# main.net
KiCad netlist of a schematic drawn in EAGLE
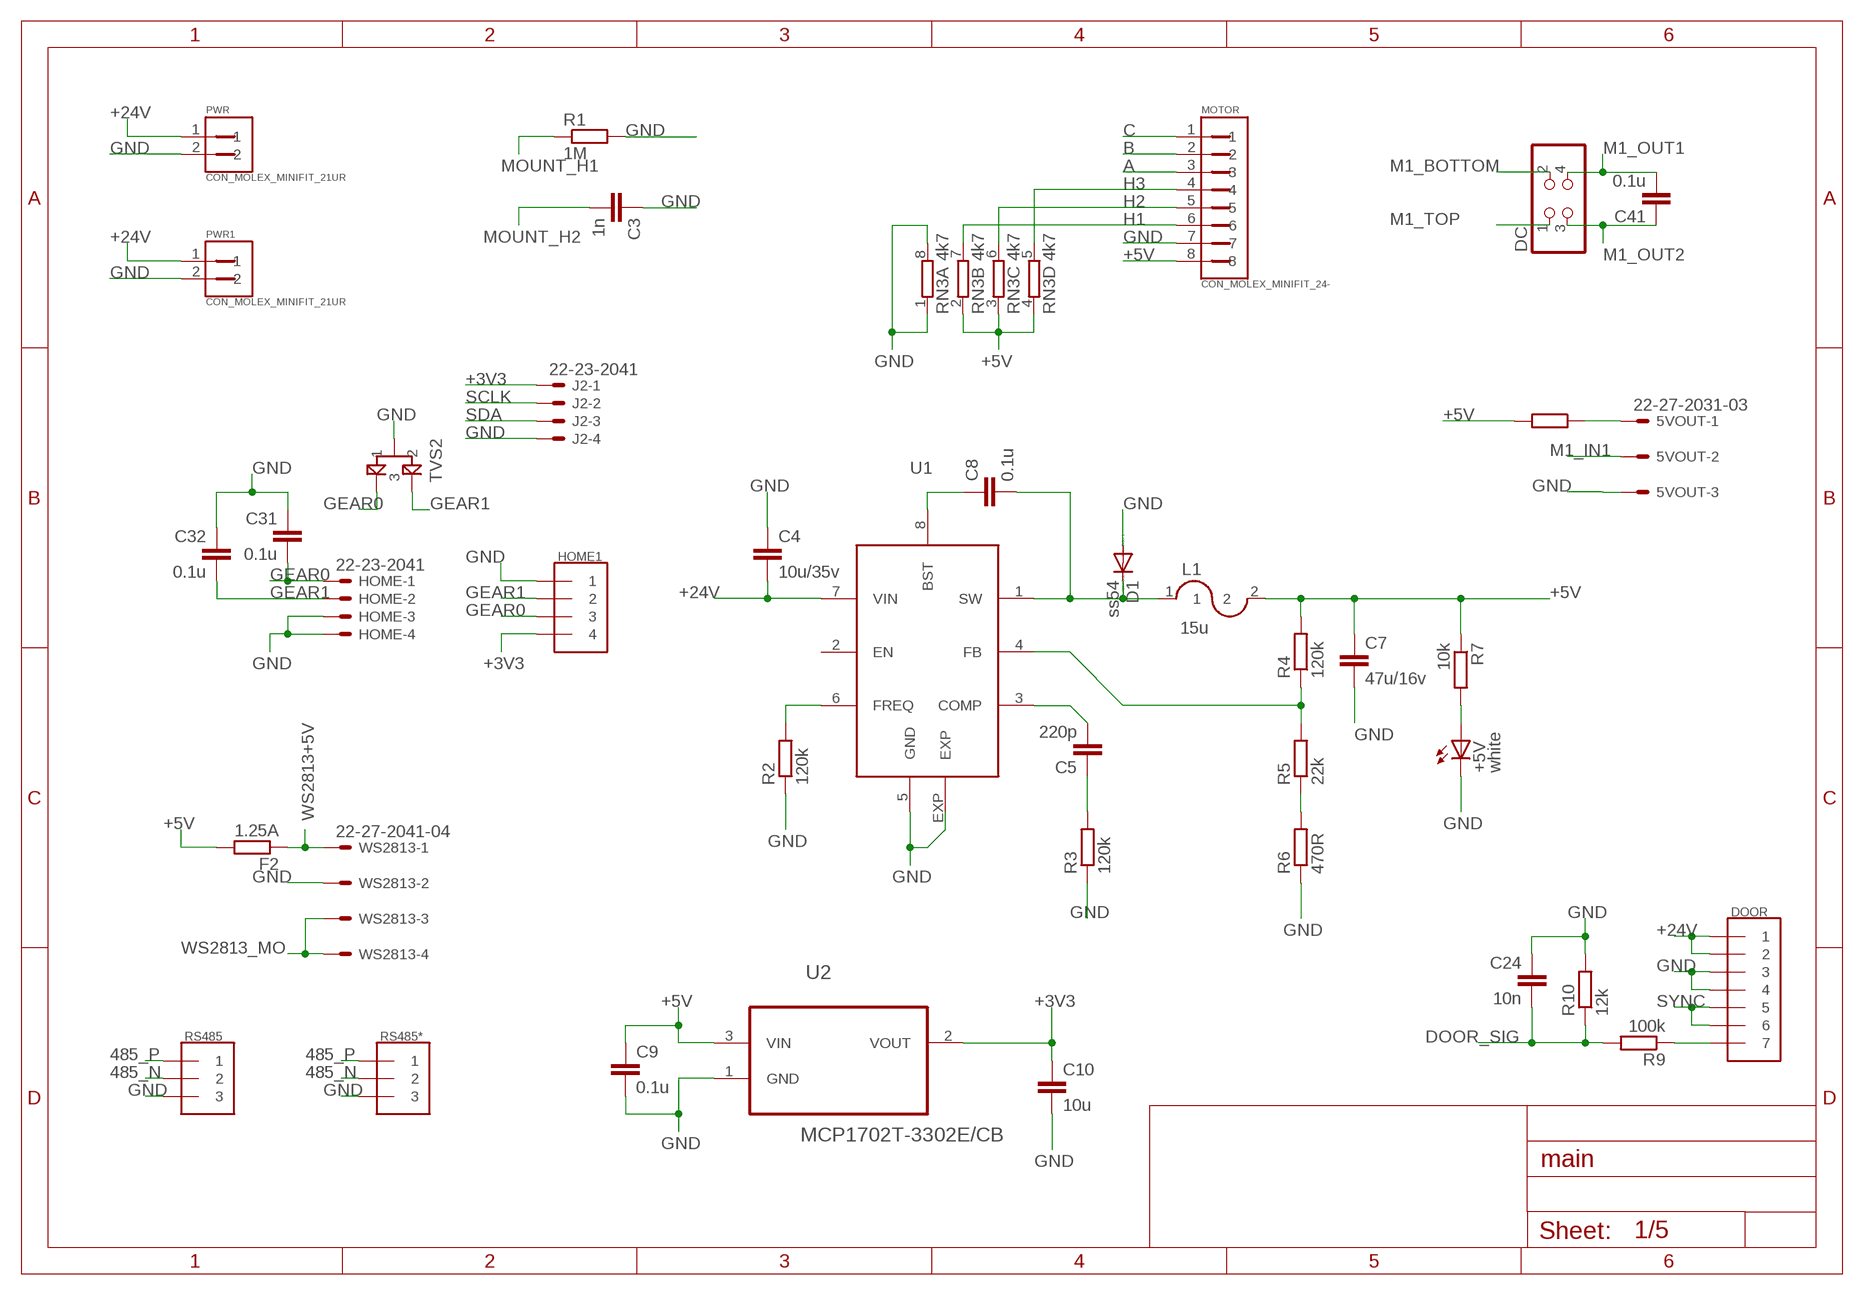
[diagram p0: schematic, sheet 1]
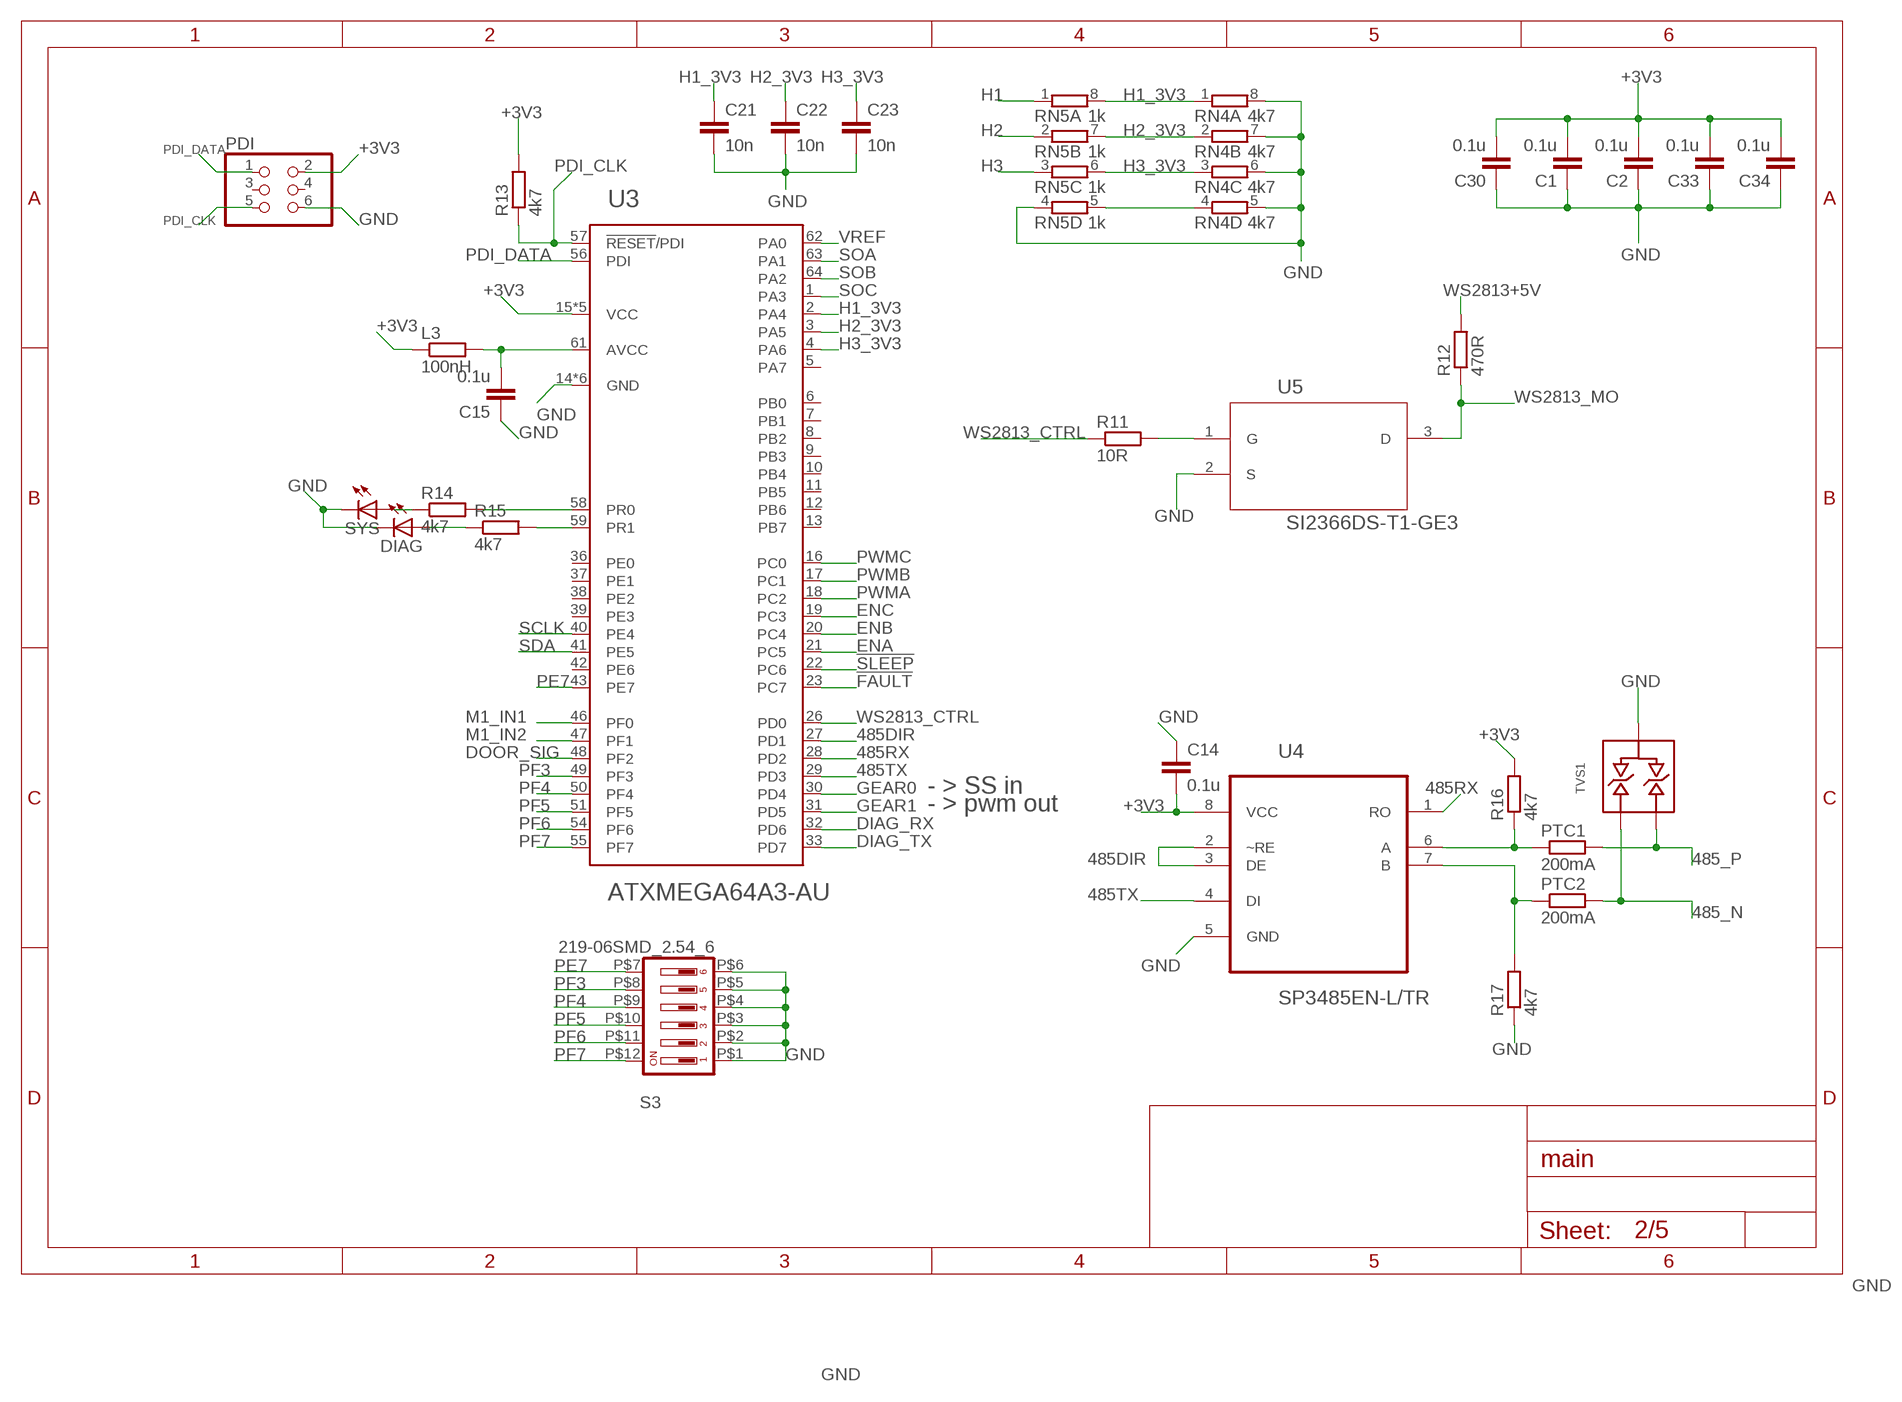
[diagram p1: schematic, sheet 2]
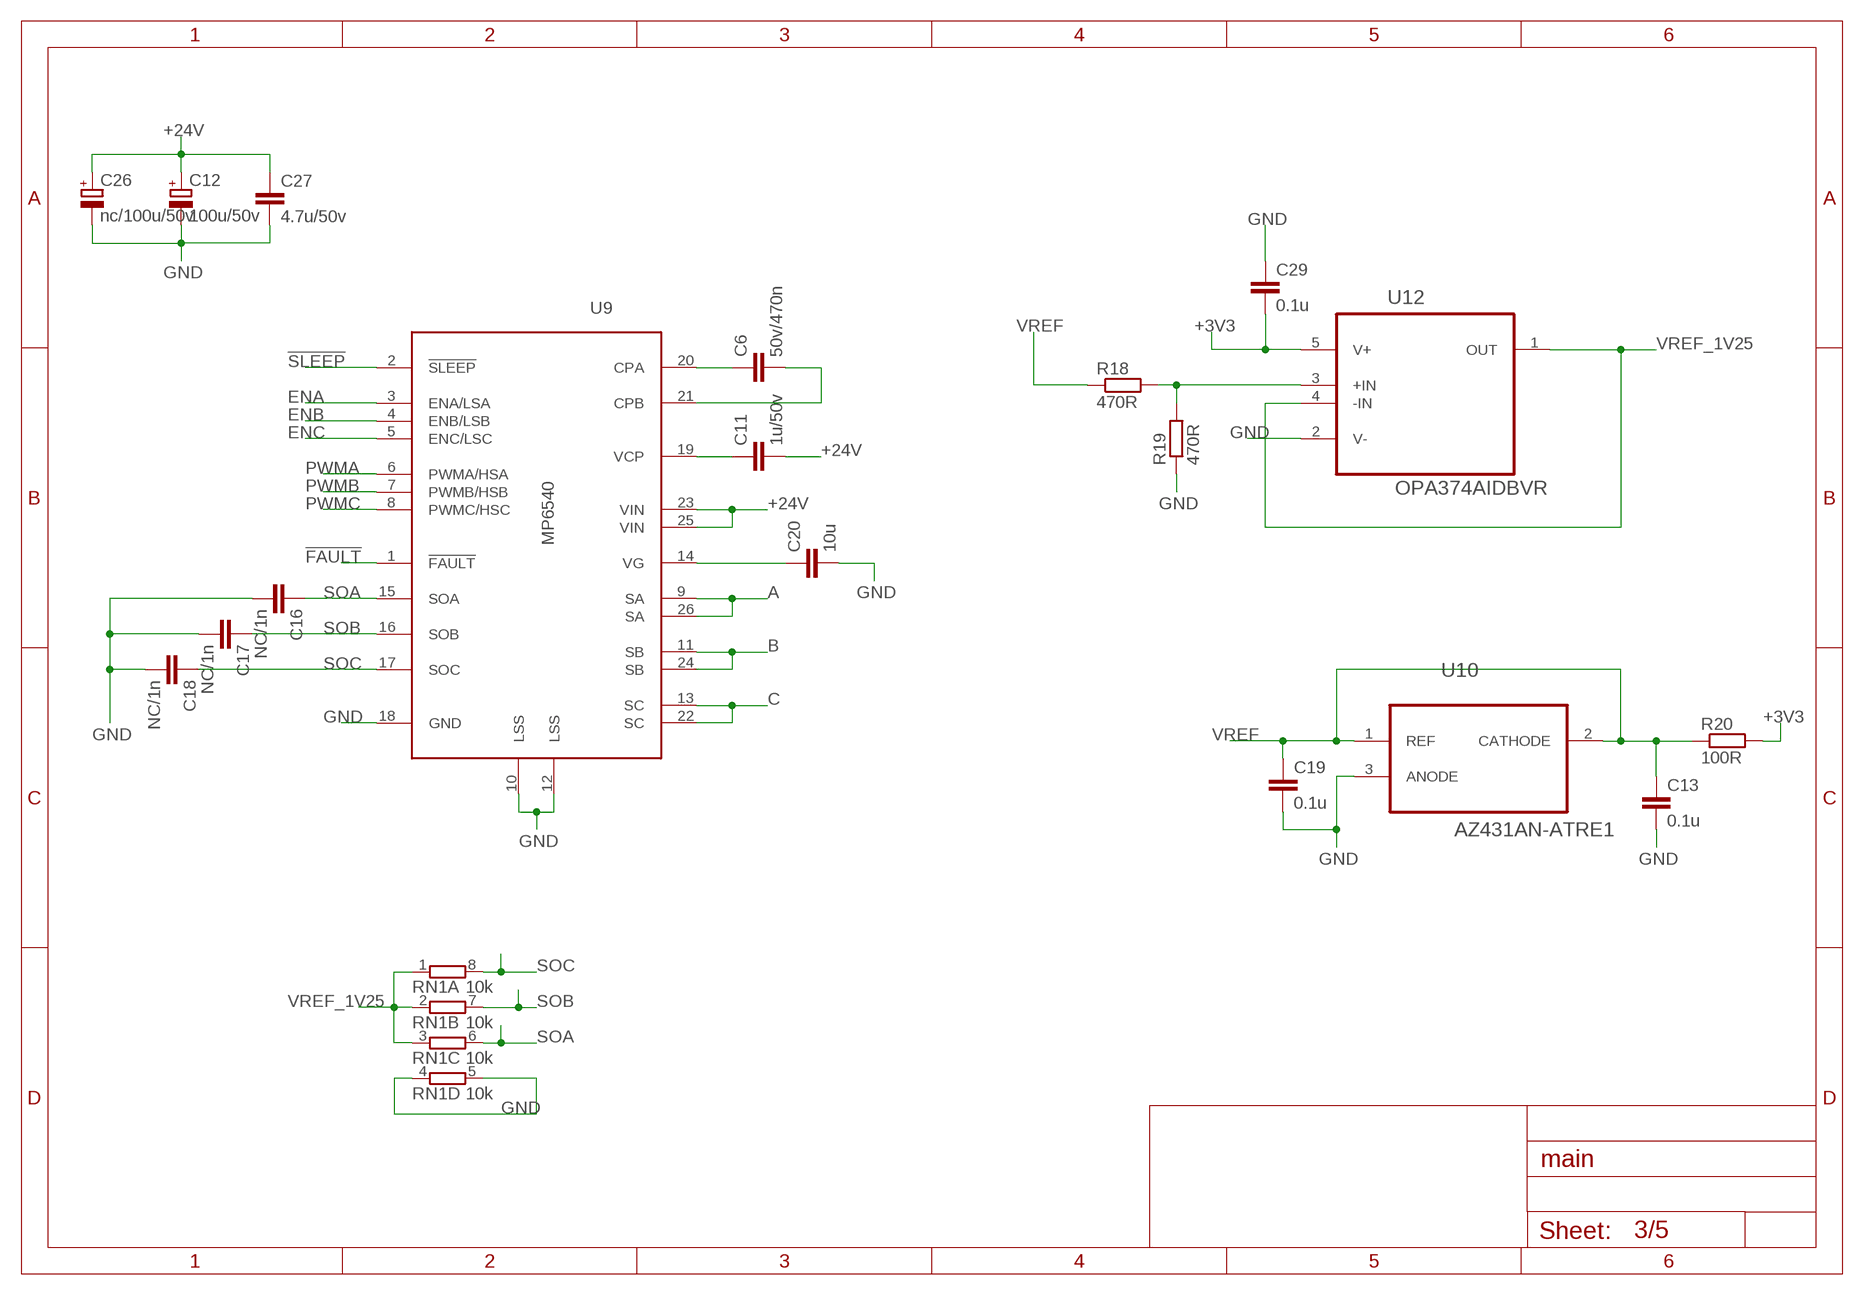
[diagram p2: schematic, sheet 3]
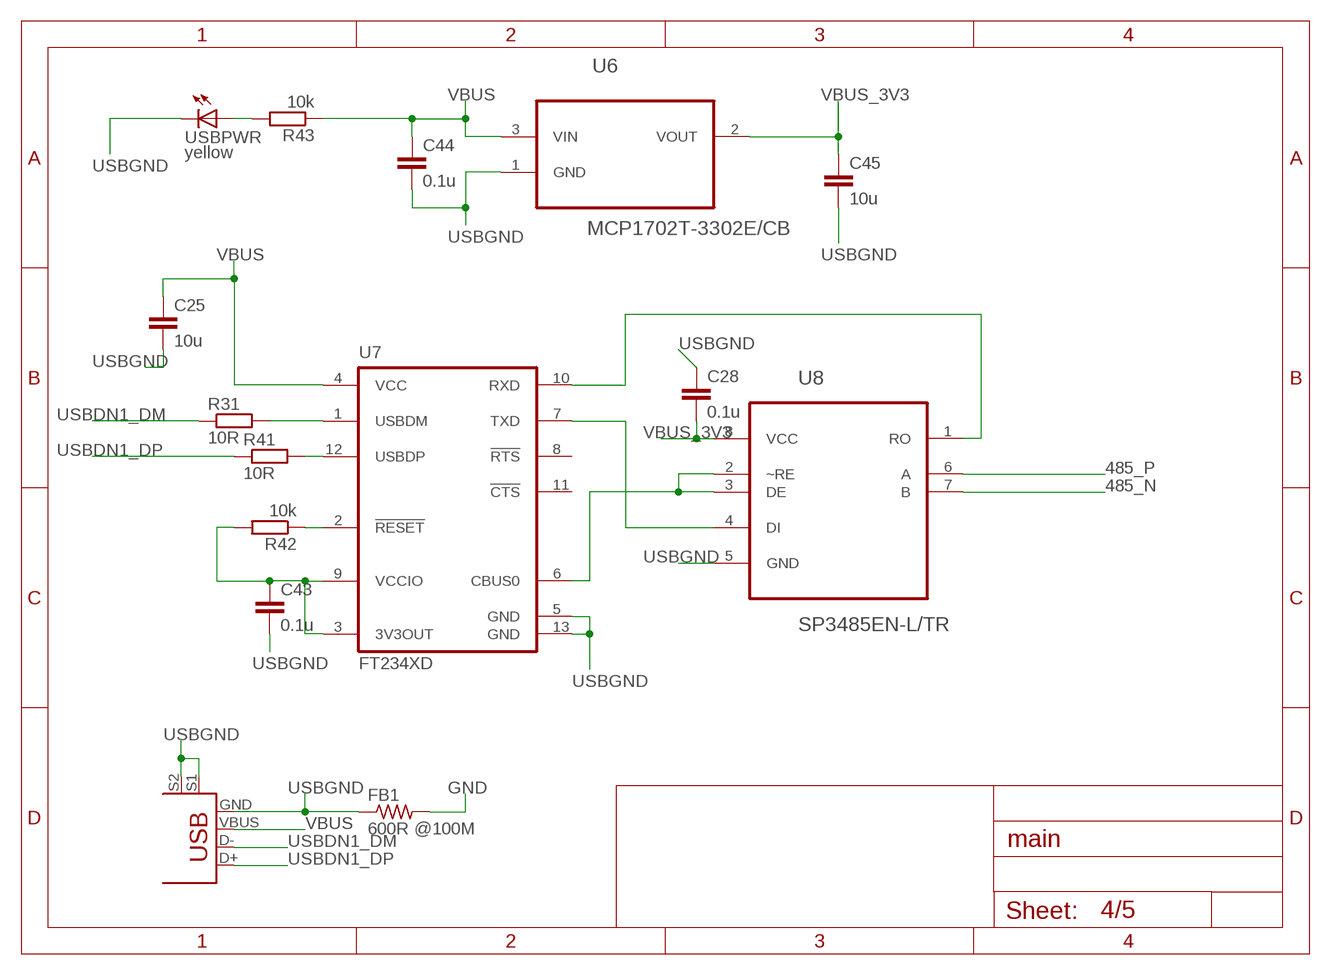
[diagram p3: schematic, sheet 4]
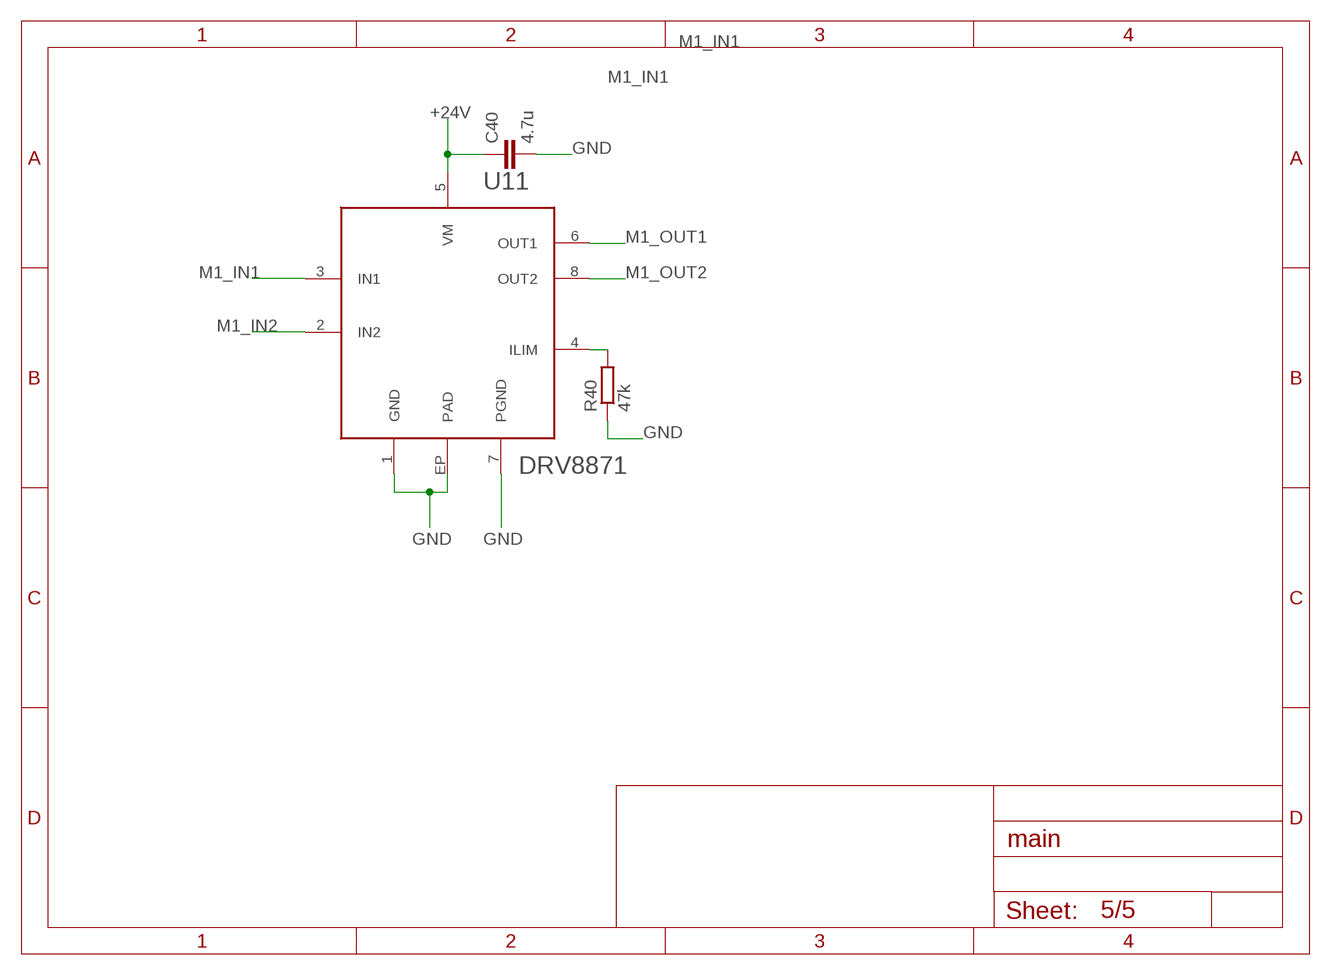
[diagram p4: schematic, sheet 5]

(export (version "E")
  (design (tool "Eeschema 10.0.6"))
  (components
    (comp (ref "C1")
      (value "0.1u")
      (footprint "eagle-import:C0603")
      (libsource (lib "eagle-import") (part "C-EUC0603"))
    )
    (comp (ref "C2")
      (value "0.1u")
      (footprint "eagle-import:C0603")
      (libsource (lib "eagle-import") (part "C-EUC0603"))
    )
    (comp (ref "C14")
      (value "0.1u")
      (footprint "eagle-import:C0603")
      (libsource (lib "eagle-import") (part "C-EUC0603"))
    )
    (comp (ref "C15")
      (value "0.1u")
      (footprint "eagle-import:C0603")
      (libsource (lib "eagle-import") (part "C-EUC0603"))
    )
    (comp (ref "C21")
      (value "10n")
      (footprint "eagle-import:C0603")
      (libsource (lib "eagle-import") (part "C-EUC0603"))
    )
    (comp (ref "C22")
      (value "10n")
      (footprint "eagle-import:C0603")
      (libsource (lib "eagle-import") (part "C-EUC0603"))
    )
    (comp (ref "C23")
      (value "10n")
      (footprint "eagle-import:C0603")
      (libsource (lib "eagle-import") (part "C-EUC0603"))
    )
    (comp (ref "C30")
      (value "0.1u")
      (footprint "eagle-import:C0603")
      (libsource (lib "eagle-import") (part "C-EUC0603"))
    )
    (comp (ref "C33")
      (value "0.1u")
      (footprint "eagle-import:C0603")
      (libsource (lib "eagle-import") (part "C-EUC0603"))
    )
    (comp (ref "C34")
      (value "0.1u")
      (footprint "eagle-import:C0603")
      (libsource (lib "eagle-import") (part "C-EUC0603"))
    )
    (comp (ref "DIAG")
      (value "LEDSML0603")
      (footprint "eagle-import:SML0603")
      (libsource (lib "eagle-import") (part "LEDSML0603"))
    )
    (comp (ref "L3")
      (value "100nH")
      (footprint "eagle-import:R0603")
      (libsource (lib "eagle-import") (part "R-EU_R0603"))
    )
    (comp (ref "PDI")
      (value "PINHD-2X3")
      (footprint "eagle-import:2X03")
      (libsource (lib "eagle-import") (part "PINHD-2X3"))
    )
    (comp (ref "PTC1")
      (value "200mA")
      (footprint "eagle-import:R0805")
      (libsource (lib "eagle-import") (part "R-EU_R0805"))
    )
    (comp (ref "PTC2")
      (value "200mA")
      (footprint "eagle-import:R0805")
      (libsource (lib "eagle-import") (part "R-EU_R0805"))
    )
    (comp (ref "R11")
      (value "10R")
      (footprint "eagle-import:R0603")
      (libsource (lib "eagle-import") (part "R-EU_R0603"))
    )
    (comp (ref "R12")
      (value "470R")
      (footprint "eagle-import:R0603")
      (libsource (lib "eagle-import") (part "R-EU_R0603"))
    )
    (comp (ref "R13")
      (value "4k7")
      (footprint "eagle-import:R0603")
      (libsource (lib "eagle-import") (part "R-EU_R0603"))
    )
    (comp (ref "R14")
      (value "4k7")
      (footprint "eagle-import:R0603")
      (libsource (lib "eagle-import") (part "R-EU_R0603"))
    )
    (comp (ref "R15")
      (value "4k7")
      (footprint "eagle-import:R0603")
      (libsource (lib "eagle-import") (part "R-EU_R0603"))
    )
    (comp (ref "R16")
      (value "4k7")
      (footprint "eagle-import:R0603")
      (libsource (lib "eagle-import") (part "R-EU_R0603"))
    )
    (comp (ref "R17")
      (value "4k7")
      (footprint "eagle-import:R0603")
      (libsource (lib "eagle-import") (part "R-EU_R0603"))
    )
    (comp (ref "RN4")
      (value "4k7")
      (footprint "eagle-import:EXB38V")
      (libsource (lib "eagle-import") (part "4R-NEXB38V"))
    )
    (comp (ref "RN5")
      (value "1k")
      (footprint "eagle-import:EXB38V")
      (libsource (lib "eagle-import") (part "4R-NEXB38V"))
    )
    (comp (ref "S3")
      (value "219-06SMD_2.54_6")
      (footprint "eagle-import:SMD-2.54-6")
      (libsource (lib "eagle-import") (part "219-06SMD_2.54_6"))
    )
    (comp (ref "SYS")
      (value "LEDSML0603")
      (footprint "eagle-import:SML0603")
      (libsource (lib "eagle-import") (part "LEDSML0603"))
    )
    (comp (ref "TVS1")
      (value "SM712")
      (footprint "eagle-import:SOT23")
      (libsource (lib "eagle-import") (part "SM712"))
    )
    (comp (ref "U3")
      (value "ATXMEGA64A3-AU")
      (footprint "eagle-import:TQFP-64A-64")
      (libsource (lib "eagle-import") (part "ATXMEGA64A3-AU"))
    )
    (comp (ref "U4")
      (value "SP3485EN-L/TR")
      (footprint "eagle-import:SOIC127P600X175-8N")
      (fields (field (name "MPN") "MAX3485CSA+"))
      (libsource (lib "eagle-import") (part "MAX3485CSA+"))
    )
    (comp (ref "U5")
      (value "SI2366DS-T1-GE3")
      (footprint "eagle-import:SOT95P237X112-3N")
      (libsource (lib "eagle-import") (part "SI2366DS-T1-GE3"))
    )
    (comp (ref "C25")
      (value "10u")
      (footprint "eagle-import:C0603")
      (libsource (lib "eagle-import") (part "C-EUC0603"))
    )
    (comp (ref "C28")
      (value "0.1u")
      (footprint "eagle-import:C0603")
      (libsource (lib "eagle-import") (part "C-EUC0603"))
    )
    (comp (ref "C43")
      (value "0.1u")
      (footprint "eagle-import:C0603")
      (libsource (lib "eagle-import") (part "C-EUC0603"))
    )
    (comp (ref "C44")
      (value "0.1u")
      (footprint "eagle-import:C0603")
      (libsource (lib "eagle-import") (part "C-EUC0603"))
    )
    (comp (ref "C45")
      (value "10u")
      (footprint "eagle-import:C0603")
      (libsource (lib "eagle-import") (part "C-EUC0603"))
    )
    (comp (ref "FB1")
      (value "600R @100M")
      (footprint "eagle-import:R0805")
      (libsource (lib "eagle-import") (part "R-US_R0805"))
    )
    (comp (ref "R31")
      (value "10R")
      (footprint "eagle-import:R0603")
      (libsource (lib "eagle-import") (part "R-EU_R0603"))
    )
    (comp (ref "R41")
      (value "10R")
      (footprint "eagle-import:R0603")
      (libsource (lib "eagle-import") (part "R-EU_R0603"))
    )
    (comp (ref "R42")
      (value "10k")
      (footprint "eagle-import:R0603")
      (libsource (lib "eagle-import") (part "R-EU_R0603"))
    )
    (comp (ref "R43")
      (value "10k")
      (footprint "eagle-import:R0603")
      (libsource (lib "eagle-import") (part "R-EU_R0603"))
    )
    (comp (ref "U6")
      (value "MCP1702T-3302E/CB")
      (footprint "eagle-import:SOT95P255X145-3N")
      (libsource (lib "eagle-import") (part "MCP1702T-3302E/CB"))
    )
    (comp (ref "U7")
      (value "FT234XD")
      (footprint "eagle-import:DFN12")
      (libsource (lib "eagle-import") (part "FT234XD"))
    )
    (comp (ref "U8")
      (value "SP3485EN-L/TR")
      (footprint "eagle-import:SOIC127P600X175-8N")
      (fields (field (name "MPN") "MAX3485CSA+"))
      (libsource (lib "eagle-import") (part "MAX3485CSA+"))
    )
    (comp (ref "USBPWR")
      (value "yellow")
      (footprint "eagle-import:SML0603")
      (libsource (lib "eagle-import") (part "LEDSML0603"))
    )
    (comp (ref "USBUP")
      (value "USB+SHIELD")
      (footprint "eagle-import:USB-B-PTH")
      (libsource (lib "eagle-import") (part "USB+SHIELD"))
    )
    (comp (ref "C40")
      (value "4.7u")
      (footprint "eagle-import:C0805")
      (libsource (lib "eagle-import") (part "C-EUC0805"))
    )
    (comp (ref "R40")
      (value "47k")
      (footprint "eagle-import:R0603")
      (libsource (lib "eagle-import") (part "R-EU_R0603"))
    )
    (comp (ref "U11")
      (value "DRV8871")
      (footprint "eagle-import:8HSOIC")
      (libsource (lib "eagle-import") (part "DRV8871"))
    )
    (comp (ref "+5V")
      (value "white")
      (footprint "eagle-import:SML0603")
      (libsource (lib "eagle-import") (part "LEDSML0603"))
    )
    (comp (ref "5VOUT")
      (value "22-27-2031-03")
      (footprint "eagle-import:6410-03")
      (libsource (lib "eagle-import") (part "22-?-0327-2031"))
    )
    (comp (ref "C3")
      (value "1n")
      (footprint "eagle-import:C0603")
      (libsource (lib "eagle-import") (part "C-EUC0603"))
    )
    (comp (ref "C4")
      (value "10u/35v")
      (footprint "eagle-import:C1206")
      (libsource (lib "eagle-import") (part "C-EUC1206"))
    )
    (comp (ref "C5")
      (value "220p")
      (footprint "eagle-import:C0603")
      (libsource (lib "eagle-import") (part "C-EUC0603"))
    )
    (comp (ref "C7")
      (value "47u/16v")
      (footprint "eagle-import:C1206")
      (libsource (lib "eagle-import") (part "C-EUC1206"))
    )
    (comp (ref "C8")
      (value "0.1u")
      (footprint "eagle-import:C0603")
      (libsource (lib "eagle-import") (part "C-EUC0603"))
    )
    (comp (ref "C9")
      (value "0.1u")
      (footprint "eagle-import:C0603")
      (libsource (lib "eagle-import") (part "C-EUC0603"))
    )
    (comp (ref "C10")
      (value "10u")
      (footprint "eagle-import:C0603")
      (libsource (lib "eagle-import") (part "C-EUC0603"))
    )
    (comp (ref "C24")
      (value "10n")
      (footprint "eagle-import:C0603")
      (libsource (lib "eagle-import") (part "C-EUC0603"))
    )
    (comp (ref "C31")
      (value "0.1u")
      (footprint "eagle-import:C0603")
      (libsource (lib "eagle-import") (part "C-EUC0603"))
    )
    (comp (ref "C32")
      (value "0.1u")
      (footprint "eagle-import:C0603")
      (libsource (lib "eagle-import") (part "C-EUC0603"))
    )
    (comp (ref "C41")
      (value "0.1u")
      (footprint "eagle-import:C0603")
      (libsource (lib "eagle-import") (part "C-EUC0603"))
    )
    (comp (ref "D1")
      (value "ss54")
      (footprint "eagle-import:DO214BA")
      (libsource (lib "eagle-import") (part "DIODE-DO214BA"))
    )
    (comp (ref "DC")
      (value "430450414")
      (footprint "eagle-import:4304504-TH")
      (libsource (lib "eagle-import") (part "430450414"))
    )
    (comp (ref "DOOR")
      (value "1LINE_SOCKET_2MM_7")
      (footprint "eagle-import:1LINE_SOCKET_2MM_7")
      (libsource (lib "eagle-import") (part "1LINE_SOCKET_2MM_7"))
    )
    (comp (ref "F1")
      (value "1.25A")
      (footprint "eagle-import:R1206")
      (libsource (lib "eagle-import") (part "R-EU_R1206"))
    )
    (comp (ref "F2")
      (value "1.25A")
      (footprint "eagle-import:R1206")
      (libsource (lib "eagle-import") (part "R-EU_R1206"))
    )
    (comp (ref "HOME")
      (value "22-23-2041")
      (footprint "eagle-import:22-23-2041")
      (fields (field (name "MF") "MOLEX"))
      (libsource (lib "eagle-import") (part "22-23-2041"))
    )
    (comp (ref "HOME1")
      (value "1LINE_SOCKET_2MM_4_90")
      (footprint "eagle-import:1LINE_SOCKET_2MM_4_90")
      (libsource (lib "eagle-import") (part "1LINE_SOCKET_2MM_4_90"))
    )
    (comp (ref "J2")
      (value "22-23-2041")
      (footprint "eagle-import:22-23-2041")
      (fields (field (name "MF") "MOLEX"))
      (libsource (lib "eagle-import") (part "con-molex_165_22-23-2041"))
    )
    (comp (ref "L1")
      (value "15u")
      (footprint "eagle-import:RCL_L_CDRH8D38")
      (libsource (lib "eagle-import") (part "RCL_L_CDRH8D38"))
    )
    (comp (ref "MOTOR")
      (value "CON_MOLEX_MINIFIT_24-")
      (footprint "eagle-import:CON_MOLEX_MINIFIT_2_4")
      (libsource (lib "eagle-import") (part "CON_MOLEX_MINIFIT_24-"))
    )
    (comp (ref "PWR")
      (value "CON_MOLEX_MINIFIT_21UR")
      (footprint "eagle-import:CON_MOLEX_MINIFIT_2_1_UR")
      (libsource (lib "eagle-import") (part "CON_MOLEX_MINIFIT_21UR"))
    )
    (comp (ref "PWR1")
      (value "CON_MOLEX_MINIFIT_21UR")
      (footprint "eagle-import:CON_MOLEX_MINIFIT_2_1_UR")
      (libsource (lib "eagle-import") (part "CON_MOLEX_MINIFIT_21UR"))
    )
    (comp (ref "R1")
      (value "1M")
      (footprint "eagle-import:R0603")
      (libsource (lib "eagle-import") (part "R-EU_R0603"))
    )
    (comp (ref "R2")
      (value "120k")
      (footprint "eagle-import:R0603")
      (libsource (lib "eagle-import") (part "R-EU_R0603"))
    )
    (comp (ref "R3")
      (value "120k")
      (footprint "eagle-import:R0603")
      (libsource (lib "eagle-import") (part "R-EU_R0603"))
    )
    (comp (ref "R4")
      (value "120k")
      (footprint "eagle-import:R0603")
      (libsource (lib "eagle-import") (part "R-EU_R0603"))
    )
    (comp (ref "R5")
      (value "22k")
      (footprint "eagle-import:R0603")
      (libsource (lib "eagle-import") (part "R-EU_R0603"))
    )
    (comp (ref "R6")
      (value "470R")
      (footprint "eagle-import:R0603")
      (libsource (lib "eagle-import") (part "R-EU_R0603"))
    )
    (comp (ref "R7")
      (value "10k")
      (footprint "eagle-import:R0603")
      (libsource (lib "eagle-import") (part "R-EU_R0603"))
    )
    (comp (ref "R9")
      (value "100k")
      (footprint "eagle-import:R0603")
      (libsource (lib "eagle-import") (part "R-EU_R0603"))
    )
    (comp (ref "R10")
      (value "12k")
      (footprint "eagle-import:R0603")
      (libsource (lib "eagle-import") (part "R-EU_R0603"))
    )
    (comp (ref "RN3")
      (value "4k7")
      (footprint "eagle-import:EXB38V")
      (libsource (lib "eagle-import") (part "4R-NEXB38V"))
    )
    (comp (ref "RS485")
      (value "1LINE_SOCKET_2MM_3_90")
      (footprint "eagle-import:1LINE_SOCKET_2MM_3_90")
      (libsource (lib "eagle-import") (part "1LINE_SOCKET_2MM_3_90"))
    )
    (comp (ref "RS485*")
      (value "1LINE_SOCKET_2MM_3_90")
      (footprint "eagle-import:1LINE_SOCKET_2MM_3_90")
      (libsource (lib "eagle-import") (part "1LINE_SOCKET_2MM_3_90"))
    )
    (comp (ref "TVS2")
      (value "PESD33")
      (footprint "eagle-import:RCL_SOT23")
      (libsource (lib "eagle-import") (part "GSOT05C-GS08"))
    )
    (comp (ref "U1")
      (value "MP2560")
      (footprint "eagle-import:SOIC-8E")
      (libsource (lib "eagle-import") (part "MP2560"))
    )
    (comp (ref "U2")
      (value "MCP1702T-3302E/CB")
      (footprint "eagle-import:SOT95P255X145-3N")
      (libsource (lib "eagle-import") (part "MCP1702T-3302E/CB"))
    )
    (comp (ref "WS2813")
      (value "22-27-2041-04")
      (footprint "eagle-import:6410-04")
      (libsource (lib "eagle-import") (part "22-?-0427-2041"))
    )
    (comp (ref "C6")
      (value "50v/470n")
      (footprint "eagle-import:C0603")
      (libsource (lib "eagle-import") (part "C-EUC0603"))
    )
    (comp (ref "C11")
      (value "1u/50v")
      (footprint "eagle-import:C0805")
      (libsource (lib "eagle-import") (part "C-EUC0805"))
    )
    (comp (ref "C12")
      (value "100u/50v")
      (footprint "eagle-import:140CLH-0810")
      (libsource (lib "eagle-import") (part "CPOL-EU140CLH-0810"))
    )
    (comp (ref "C13")
      (value "0.1u")
      (footprint "eagle-import:C0603")
      (libsource (lib "eagle-import") (part "C-EUC0603"))
    )
    (comp (ref "C16")
      (value "NC/1n")
      (footprint "eagle-import:C0603")
      (libsource (lib "eagle-import") (part "C-EUC0603"))
    )
    (comp (ref "C17")
      (value "NC/1n")
      (footprint "eagle-import:C0603")
      (libsource (lib "eagle-import") (part "C-EUC0603"))
    )
    (comp (ref "C18")
      (value "NC/1n")
      (footprint "eagle-import:C0603")
      (libsource (lib "eagle-import") (part "C-EUC0603"))
    )
    (comp (ref "C19")
      (value "0.1u")
      (footprint "eagle-import:C0603")
      (libsource (lib "eagle-import") (part "C-EUC0603"))
    )
    (comp (ref "C20")
      (value "10u")
      (footprint "eagle-import:C0603")
      (libsource (lib "eagle-import") (part "C-EUC0603"))
    )
    (comp (ref "C26")
      (value "nc/100u/50v")
      (footprint "eagle-import:140CLH-0810")
      (libsource (lib "eagle-import") (part "CPOL-EU140CLH-0810"))
    )
    (comp (ref "C27")
      (value "4.7u/50v")
      (footprint "eagle-import:C0805")
      (libsource (lib "eagle-import") (part "C-EUC0805"))
    )
    (comp (ref "C29")
      (value "0.1u")
      (footprint "eagle-import:C0603")
      (libsource (lib "eagle-import") (part "C-EUC0603"))
    )
    (comp (ref "R18")
      (value "470R")
      (footprint "eagle-import:R0603")
      (libsource (lib "eagle-import") (part "R-EU_R0603"))
    )
    (comp (ref "R19")
      (value "470R")
      (footprint "eagle-import:R0603")
      (libsource (lib "eagle-import") (part "R-EU_R0603"))
    )
    (comp (ref "R20")
      (value "100R")
      (footprint "eagle-import:R0603")
      (libsource (lib "eagle-import") (part "R-EU_R0603"))
    )
    (comp (ref "RN1")
      (value "10k")
      (footprint "eagle-import:EXB38V")
      (libsource (lib "eagle-import") (part "4R-NEXB38V"))
    )
    (comp (ref "U9")
      (value "MP6540")
      (footprint "eagle-import:QFN-26")
      (libsource (lib "eagle-import") (part "MP6540"))
    )
    (comp (ref "U10")
      (value "AZ431AN-ATRE1")
      (footprint "eagle-import:SOT95P237X112-3N")
      (fields (field (name "MPN") "TL431BQDBZR"))
      (libsource (lib "eagle-import") (part "TL431BQDBZR"))
    )
    (comp (ref "U12")
      (value "OPA374AIDBVR")
      (footprint "eagle-import:SOT95P280X145-5N")
      (fields (field (name "MPN") "OPA378AIDBVT"))
      (libsource (lib "eagle-import") (part "OPA378AIDBVT"))
    )
  )
  (nets
    (net (code "1") (name "+3V3") (class "Default")
      (node (ref "C1") (pin "2") (pinfunction "2_2") (pintype "passive"))
      (node (ref "C10") (pin "1") (pinfunction "1_1") (pintype "passive"))
      (node (ref "C14") (pin "2") (pinfunction "2_2") (pintype "passive"))
      (node (ref "C2") (pin "2") (pinfunction "2_2") (pintype "passive"))
      (node (ref "C29") (pin "2") (pinfunction "2_2") (pintype "passive"))
      (node (ref "C30") (pin "2") (pinfunction "2_2") (pintype "passive"))
      (node (ref "C33") (pin "2") (pinfunction "2_2") (pintype "passive"))
      (node (ref "C34") (pin "2") (pinfunction "2_2") (pintype "passive"))
      (node (ref "HOME1") (pin "P$4") (pinfunction "4_P$4") (pintype "passive"))
      (node (ref "J2") (pin "1") (pinfunction "S_1") (pintype "passive"))
      (node (ref "L3") (pin "1") (pinfunction "1_1") (pintype "passive"))
      (node (ref "PDI") (pin "2") (pinfunction "2_2") (pintype "passive"))
      (node (ref "R13") (pin "2") (pinfunction "2_2") (pintype "passive"))
      (node (ref "R16") (pin "2") (pinfunction "2_2") (pintype "passive"))
      (node (ref "R20") (pin "2") (pinfunction "2_2") (pintype "passive"))
      (node (ref "U12") (pin "5") (pinfunction "V+_5") (pintype "power_in"))
      (node (ref "U2") (pin "2") (pinfunction "VOUT_2") (pintype "output"))
      (node (ref "U3") (pin "15") (pinfunction "VCC_15") (pintype "power_in"))
      (node (ref "U3") (pin "25") (pinfunction "VCC_25") (pintype "power_in"))
      (node (ref "U3") (pin "35") (pinfunction "VCC_35") (pintype "power_in"))
      (node (ref "U3") (pin "45") (pinfunction "VCC_45") (pintype "power_in"))
      (node (ref "U3") (pin "53") (pinfunction "VCC_53") (pintype "power_in"))
      (node (ref "U4") (pin "8") (pinfunction "VCC_8") (pintype "power_in"))
    )
    (net (code "2") (name "+5V") (class "Default")
      (node (ref "C7") (pin "1") (pinfunction "1_1") (pintype "passive"))
      (node (ref "C9") (pin "1") (pinfunction "1_1") (pintype "passive"))
      (node (ref "F1") (pin "2") (pinfunction "2_2") (pintype "passive"))
      (node (ref "F2") (pin "2") (pinfunction "2_2") (pintype "passive"))
      (node (ref "L1") (pin "2") (pinfunction "2_2") (pintype "bidirectional"))
      (node (ref "MOTOR") (pin "8") (pinfunction "8_8") (pintype "passive"))
      (node (ref "R4") (pin "2") (pinfunction "2_2") (pintype "passive"))
      (node (ref "R7") (pin "1") (pinfunction "1_1") (pintype "passive"))
      (node (ref "RN3") (pin "2") (pinfunction "1_2") (pintype "passive"))
      (node (ref "RN3") (pin "3") (pinfunction "1_3") (pintype "passive"))
      (node (ref "RN3") (pin "4") (pinfunction "1_4") (pintype "passive"))
      (node (ref "U2") (pin "3") (pinfunction "VIN_3") (pintype "input"))
    )
    (net (code "3") (name "+24V") (class "Default")
      (node (ref "C11") (pin "2") (pinfunction "2_2") (pintype "passive"))
      (node (ref "C12") (pin "+") (pinfunction "+_+") (pintype "passive"))
      (node (ref "C26") (pin "+") (pinfunction "+_+") (pintype "passive"))
      (node (ref "C27") (pin "1") (pinfunction "1_1") (pintype "passive"))
      (node (ref "C4") (pin "2") (pinfunction "2_2") (pintype "passive"))
      (node (ref "C40") (pin "1") (pinfunction "1_1") (pintype "passive"))
      (node (ref "DOOR") (pin "P$1") (pinfunction "1_P$1") (pintype "passive"))
      (node (ref "DOOR") (pin "P$2") (pinfunction "2_P$2") (pintype "passive"))
      (node (ref "PWR") (pin "1") (pinfunction "1_1") (pintype "passive"))
      (node (ref "PWR1") (pin "1") (pinfunction "1_1") (pintype "passive"))
      (node (ref "U1") (pin "7") (pinfunction "VIN_7") (pintype "bidirectional"))
      (node (ref "U11") (pin "5") (pinfunction "VM_5") (pintype "bidirectional"))
      (node (ref "U9") (pin "23") (pinfunction "VIN_23") (pintype "bidirectional"))
      (node (ref "U9") (pin "25") (pinfunction "VIN_25") (pintype "bidirectional"))
    )
    (net (code "4") (name "485DIR") (class "Default")
      (node (ref "U3") (pin "27") (pinfunction "PD1_27") (pintype "bidirectional"))
      (node (ref "U4") (pin "2") (pinfunction "~{RE}_2") (pintype "input"))
      (node (ref "U4") (pin "3") (pinfunction "DE_3") (pintype "input"))
    )
    (net (code "5") (name "485RX") (class "Default")
      (node (ref "U3") (pin "28") (pinfunction "PD2_28") (pintype "bidirectional"))
      (node (ref "U4") (pin "1") (pinfunction "RO_1") (pintype "output"))
    )
    (net (code "6") (name "485TX") (class "Default")
      (node (ref "U3") (pin "29") (pinfunction "PD3_29") (pintype "bidirectional"))
      (node (ref "U4") (pin "4") (pinfunction "DI_4") (pintype "input"))
    )
    (net (code "7") (name "485_N") (class "Default")
      (node (ref "PTC2") (pin "2") (pinfunction "2_2") (pintype "passive"))
      (node (ref "RS485") (pin "P$2") (pinfunction "2_P$2") (pintype "passive"))
      (node (ref "RS485*") (pin "P$2") (pinfunction "2_P$2") (pintype "passive"))
      (node (ref "TVS1") (pin "P$1") (pinfunction "P$1_P$1") (pintype "passive"))
      (node (ref "U8") (pin "7") (pinfunction "B_7") (pintype "bidirectional"))
    )
    (net (code "8") (name "485_P") (class "Default")
      (node (ref "PTC1") (pin "2") (pinfunction "2_2") (pintype "passive"))
      (node (ref "RS485") (pin "P$1") (pinfunction "1_P$1") (pintype "passive"))
      (node (ref "RS485*") (pin "P$1") (pinfunction "1_P$1") (pintype "passive"))
      (node (ref "TVS1") (pin "P$2") (pinfunction "P$2_P$2") (pintype "passive"))
      (node (ref "U8") (pin "6") (pinfunction "A_6") (pintype "bidirectional"))
    )
    (net (code "9") (name "A") (class "Default")
      (node (ref "MOTOR") (pin "3") (pinfunction "3_3") (pintype "passive"))
      (node (ref "U9") (pin "26") (pinfunction "SA_26") (pintype "bidirectional"))
      (node (ref "U9") (pin "9") (pinfunction "SA_9") (pintype "bidirectional"))
    )
    (net (code "10") (name "B") (class "Default")
      (node (ref "MOTOR") (pin "2") (pinfunction "2_2") (pintype "passive"))
      (node (ref "U9") (pin "11") (pinfunction "SB_11") (pintype "bidirectional"))
      (node (ref "U9") (pin "24") (pinfunction "SB_24") (pintype "bidirectional"))
    )
    (net (code "11") (name "C") (class "Default")
      (node (ref "MOTOR") (pin "1") (pinfunction "1_1") (pintype "passive"))
      (node (ref "U9") (pin "13") (pinfunction "SC_13") (pintype "bidirectional"))
      (node (ref "U9") (pin "22") (pinfunction "SC_22") (pintype "bidirectional"))
    )
    (net (code "12") (name "DIAG_RX") (class "Default")
      (node (ref "U3") (pin "32") (pinfunction "PD6_32") (pintype "bidirectional"))
    )
    (net (code "13") (name "DIAG_TX") (class "Default")
      (node (ref "U3") (pin "33") (pinfunction "PD7_33") (pintype "bidirectional"))
    )
    (net (code "14") (name "DOOR_SIG") (class "Default")
      (node (ref "C24") (pin "2") (pinfunction "2_2") (pintype "passive"))
      (node (ref "R10") (pin "1") (pinfunction "1_1") (pintype "passive"))
      (node (ref "R9") (pin "2") (pinfunction "2_2") (pintype "passive"))
      (node (ref "U3") (pin "48") (pinfunction "PF2_48") (pintype "bidirectional"))
    )
    (net (code "15") (name "ENA") (class "Default")
      (node (ref "U3") (pin "21") (pinfunction "PC5_21") (pintype "bidirectional"))
      (node (ref "U9") (pin "3") (pinfunction "ENA/LSA_3") (pintype "bidirectional"))
    )
    (net (code "16") (name "ENB") (class "Default")
      (node (ref "U3") (pin "20") (pinfunction "PC4_20") (pintype "bidirectional"))
      (node (ref "U9") (pin "4") (pinfunction "ENB/LSB_4") (pintype "bidirectional"))
    )
    (net (code "17") (name "ENC") (class "Default")
      (node (ref "U3") (pin "19") (pinfunction "PC3_19") (pintype "bidirectional"))
      (node (ref "U9") (pin "5") (pinfunction "ENC/LSC_5") (pintype "bidirectional"))
    )
    (net (code "18") (name "GEAR0") (class "Default")
      (node (ref "C31") (pin "2") (pinfunction "2_2") (pintype "passive"))
      (node (ref "HOME") (pin "1") (pinfunction "S_1") (pintype "passive"))
      (node (ref "HOME1") (pin "P$3") (pinfunction "3_P$3") (pintype "passive"))
      (node (ref "TVS2") (pin "1") (pinfunction "1_1") (pintype "passive"))
      (node (ref "U3") (pin "30") (pinfunction "PD4_30") (pintype "bidirectional"))
    )
    (net (code "19") (name "GEAR1") (class "Default")
      (node (ref "C32") (pin "2") (pinfunction "2_2") (pintype "passive"))
      (node (ref "HOME") (pin "2") (pinfunction "S_2") (pintype "passive"))
      (node (ref "HOME1") (pin "P$2") (pinfunction "2_P$2") (pintype "passive"))
      (node (ref "TVS2") (pin "2") (pinfunction "2_2") (pintype "passive"))
      (node (ref "U3") (pin "31") (pinfunction "PD5_31") (pintype "bidirectional"))
    )
    (net (code "20") (name "GND") (class "Default")
      (node (ref "+5V") (pin "C") (pinfunction "C_C") (pintype "passive"))
      (node (ref "5VOUT") (pin "3") (pinfunction "S_3") (pintype "passive"))
      (node (ref "C1") (pin "1") (pinfunction "1_1") (pintype "passive"))
      (node (ref "C10") (pin "2") (pinfunction "2_2") (pintype "passive"))
      (node (ref "C12") (pin "-") (pinfunction "-_-") (pintype "passive"))
      (node (ref "C13") (pin "2") (pinfunction "2_2") (pintype "passive"))
      (node (ref "C14") (pin "1") (pinfunction "1_1") (pintype "passive"))
      (node (ref "C15") (pin "1") (pinfunction "1_1") (pintype "passive"))
      (node (ref "C16") (pin "2") (pinfunction "2_2") (pintype "passive"))
      (node (ref "C17") (pin "2") (pinfunction "2_2") (pintype "passive"))
      (node (ref "C18") (pin "2") (pinfunction "2_2") (pintype "passive"))
      (node (ref "C19") (pin "2") (pinfunction "2_2") (pintype "passive"))
      (node (ref "C2") (pin "1") (pinfunction "1_1") (pintype "passive"))
      (node (ref "C20") (pin "2") (pinfunction "2_2") (pintype "passive"))
      (node (ref "C21") (pin "2") (pinfunction "2_2") (pintype "passive"))
      (node (ref "C22") (pin "2") (pinfunction "2_2") (pintype "passive"))
      (node (ref "C23") (pin "2") (pinfunction "2_2") (pintype "passive"))
      (node (ref "C24") (pin "1") (pinfunction "1_1") (pintype "passive"))
      (node (ref "C26") (pin "-") (pinfunction "-_-") (pintype "passive"))
      (node (ref "C27") (pin "2") (pinfunction "2_2") (pintype "passive"))
      (node (ref "C29") (pin "1") (pinfunction "1_1") (pintype "passive"))
      (node (ref "C3") (pin "1") (pinfunction "1_1") (pintype "passive"))
      (node (ref "C30") (pin "1") (pinfunction "1_1") (pintype "passive"))
      (node (ref "C31") (pin "1") (pinfunction "1_1") (pintype "passive"))
      (node (ref "C32") (pin "1") (pinfunction "1_1") (pintype "passive"))
      (node (ref "C33") (pin "1") (pinfunction "1_1") (pintype "passive"))
      (node (ref "C34") (pin "1") (pinfunction "1_1") (pintype "passive"))
      (node (ref "C4") (pin "1") (pinfunction "1_1") (pintype "passive"))
      (node (ref "C40") (pin "2") (pinfunction "2_2") (pintype "passive"))
      (node (ref "C7") (pin "2") (pinfunction "2_2") (pintype "passive"))
      (node (ref "C9") (pin "2") (pinfunction "2_2") (pintype "passive"))
      (node (ref "D1") (pin "A") (pinfunction "A_A") (pintype "passive"))
      (node (ref "DIAG") (pin "C") (pinfunction "C_C") (pintype "passive"))
      (node (ref "DOOR") (pin "P$3") (pinfunction "3_P$3") (pintype "passive"))
      (node (ref "DOOR") (pin "P$4") (pinfunction "4_P$4") (pintype "passive"))
      (node (ref "FB1") (pin "2") (pinfunction "2_2") (pintype "passive"))
      (node (ref "HOME") (pin "3") (pinfunction "S_3") (pintype "passive"))
      (node (ref "HOME") (pin "4") (pinfunction "S_4") (pintype "passive"))
      (node (ref "HOME1") (pin "P$1") (pinfunction "1_P$1") (pintype "passive"))
      (node (ref "J2") (pin "4") (pinfunction "S_4") (pintype "passive"))
      (node (ref "MOTOR") (pin "7") (pinfunction "7_7") (pintype "passive"))
      (node (ref "PDI") (pin "6") (pinfunction "6_6") (pintype "passive"))
      (node (ref "PWR") (pin "2") (pinfunction "2_2") (pintype "passive"))
      (node (ref "PWR1") (pin "2") (pinfunction "2_2") (pintype "passive"))
      (node (ref "R1") (pin "2") (pinfunction "2_2") (pintype "passive"))
      (node (ref "R10") (pin "2") (pinfunction "2_2") (pintype "passive"))
      (node (ref "R17") (pin "1") (pinfunction "1_1") (pintype "passive"))
      (node (ref "R19") (pin "1") (pinfunction "1_1") (pintype "passive"))
      (node (ref "R2") (pin "1") (pinfunction "1_1") (pintype "passive"))
      (node (ref "R3") (pin "1") (pinfunction "1_1") (pintype "passive"))
      (node (ref "R40") (pin "1") (pinfunction "1_1") (pintype "passive"))
      (node (ref "R6") (pin "1") (pinfunction "1_1") (pintype "passive"))
      (node (ref "RN1") (pin "4") (pinfunction "1_4") (pintype "passive"))
      (node (ref "RN1") (pin "5") (pinfunction "2_5") (pintype "passive"))
      (node (ref "RN3") (pin "1") (pinfunction "1_1") (pintype "passive"))
      (node (ref "RN3") (pin "8") (pinfunction "2_8") (pintype "passive"))
      (node (ref "RN4") (pin "4") (pinfunction "1_4") (pintype "passive"))
      (node (ref "RN4") (pin "5") (pinfunction "2_5") (pintype "passive"))
      (node (ref "RN4") (pin "6") (pinfunction "2_6") (pintype "passive"))
      (node (ref "RN4") (pin "7") (pinfunction "2_7") (pintype "passive"))
      (node (ref "RN4") (pin "8") (pinfunction "2_8") (pintype "passive"))
      (node (ref "RN5") (pin "4") (pinfunction "1_4") (pintype "passive"))
      (node (ref "RN5") (pin "5") (pinfunction "2_5") (pintype "passive"))
      (node (ref "RS485") (pin "P$3") (pinfunction "3_P$3") (pintype "passive"))
      (node (ref "RS485*") (pin "P$3") (pinfunction "3_P$3") (pintype "passive"))
      (node (ref "S3") (pin "P$1") (pinfunction "1_P$1") (pintype "passive"))
      (node (ref "S3") (pin "P$2") (pinfunction "2_P$2") (pintype "passive"))
      (node (ref "S3") (pin "P$3") (pinfunction "3_P$3") (pintype "passive"))
      (node (ref "S3") (pin "P$4") (pinfunction "4_P$4") (pintype "passive"))
      (node (ref "S3") (pin "P$5") (pinfunction "5_P$5") (pintype "passive"))
      (node (ref "S3") (pin "P$6") (pinfunction "6_P$6") (pintype "passive"))
      (node (ref "SYS") (pin "C") (pinfunction "C_C") (pintype "passive"))
      (node (ref "TVS1") (pin "P$3") (pinfunction "P$3_P$3") (pintype "passive"))
      (node (ref "TVS2") (pin "3") (pinfunction "3_3") (pintype "passive"))
      (node (ref "U1") (pin "5") (pinfunction "GND_5") (pintype "bidirectional"))
      (node (ref "U1") (pin "EXP") (pinfunction "EXP_EXP") (pintype "bidirectional"))
      (node (ref "U10") (pin "3") (pinfunction "ANODE_3") (pintype "passive"))
      (node (ref "U11") (pin "1") (pinfunction "GND_1") (pintype "bidirectional"))
      (node (ref "U11") (pin "7") (pinfunction "PGND_7") (pintype "bidirectional"))
      (node (ref "U11") (pin "EP") (pinfunction "PAD_EP") (pintype "bidirectional"))
      (node (ref "U12") (pin "2") (pinfunction "V-_2") (pintype "power_in"))
      (node (ref "U2") (pin "1") (pinfunction "GND_1") (pintype "passive"))
      (node (ref "U3") (pin "14") (pinfunction "GND_14") (pintype "power_in"))
      (node (ref "U3") (pin "24") (pinfunction "GND_24") (pintype "power_in"))
      (node (ref "U3") (pin "34") (pinfunction "GND_34") (pintype "power_in"))
      (node (ref "U3") (pin "44") (pinfunction "GND_44") (pintype "power_in"))
      (node (ref "U3") (pin "52") (pinfunction "GND_52") (pintype "power_in"))
      (node (ref "U3") (pin "60") (pinfunction "GND_60") (pintype "power_in"))
      (node (ref "U4") (pin "5") (pinfunction "GND_5") (pintype "passive"))
      (node (ref "U5") (pin "2") (pinfunction "S_2") (pintype "passive"))
      (node (ref "U9") (pin "10") (pinfunction "LSS_10") (pintype "bidirectional"))
      (node (ref "U9") (pin "12") (pinfunction "LSS_12") (pintype "bidirectional"))
      (node (ref "U9") (pin "18") (pinfunction "GND_18") (pintype "bidirectional"))
      (node (ref "WS2813") (pin "2") (pinfunction "S_2") (pintype "passive"))
    )
    (net (code "21") (name "H1") (class "Default")
      (node (ref "MOTOR") (pin "6") (pinfunction "6_6") (pintype "passive"))
      (node (ref "RN3") (pin "7") (pinfunction "2_7") (pintype "passive"))
      (node (ref "RN5") (pin "1") (pinfunction "1_1") (pintype "passive"))
    )
    (net (code "22") (name "H1_3V3") (class "Default")
      (node (ref "C21") (pin "1") (pinfunction "1_1") (pintype "passive"))
      (node (ref "RN4") (pin "1") (pinfunction "1_1") (pintype "passive"))
      (node (ref "RN5") (pin "8") (pinfunction "2_8") (pintype "passive"))
      (node (ref "U3") (pin "2") (pinfunction "PA4_2") (pintype "bidirectional"))
    )
    (net (code "23") (name "H2") (class "Default")
      (node (ref "MOTOR") (pin "5") (pinfunction "5_5") (pintype "passive"))
      (node (ref "RN3") (pin "6") (pinfunction "2_6") (pintype "passive"))
      (node (ref "RN5") (pin "2") (pinfunction "1_2") (pintype "passive"))
    )
    (net (code "24") (name "H2_3V3") (class "Default")
      (node (ref "C22") (pin "1") (pinfunction "1_1") (pintype "passive"))
      (node (ref "RN4") (pin "2") (pinfunction "1_2") (pintype "passive"))
      (node (ref "RN5") (pin "7") (pinfunction "2_7") (pintype "passive"))
      (node (ref "U3") (pin "3") (pinfunction "PA5_3") (pintype "bidirectional"))
    )
    (net (code "25") (name "H3") (class "Default")
      (node (ref "MOTOR") (pin "4") (pinfunction "4_4") (pintype "passive"))
      (node (ref "RN3") (pin "5") (pinfunction "2_5") (pintype "passive"))
      (node (ref "RN5") (pin "3") (pinfunction "1_3") (pintype "passive"))
    )
    (net (code "26") (name "H3_3V3") (class "Default")
      (node (ref "C23") (pin "1") (pinfunction "1_1") (pintype "passive"))
      (node (ref "RN4") (pin "3") (pinfunction "1_3") (pintype "passive"))
      (node (ref "RN5") (pin "6") (pinfunction "2_6") (pintype "passive"))
      (node (ref "U3") (pin "4") (pinfunction "PA6_4") (pintype "bidirectional"))
    )
    (net (code "27") (name "M1_BOTTOM") (class "Default")
      (node (ref "DC") (pin "2") (pinfunction "2_2") (pintype "passive"))
    )
    (net (code "28") (name "M1_IN1") (class "Default")
      (node (ref "5VOUT") (pin "2") (pinfunction "S_2") (pintype "passive"))
      (node (ref "U11") (pin "3") (pinfunction "IN1_3") (pintype "bidirectional"))
      (node (ref "U3") (pin "46") (pinfunction "PF0_46") (pintype "bidirectional"))
    )
    (net (code "29") (name "M1_IN2") (class "Default")
      (node (ref "U11") (pin "2") (pinfunction "IN2_2") (pintype "bidirectional"))
      (node (ref "U3") (pin "47") (pinfunction "PF1_47") (pintype "bidirectional"))
    )
    (net (code "30") (name "M1_OUT1") (class "Default")
      (node (ref "C41") (pin "2") (pinfunction "2_2") (pintype "passive"))
      (node (ref "DC") (pin "4") (pinfunction "4_4") (pintype "passive"))
      (node (ref "U11") (pin "6") (pinfunction "OUT1_6") (pintype "bidirectional"))
    )
    (net (code "31") (name "M1_OUT2") (class "Default")
      (node (ref "C41") (pin "1") (pinfunction "1_1") (pintype "passive"))
      (node (ref "DC") (pin "3") (pinfunction "3_3") (pintype "passive"))
      (node (ref "U11") (pin "8") (pinfunction "OUT2_8") (pintype "bidirectional"))
    )
    (net (code "32") (name "M1_TOP") (class "Default")
      (node (ref "DC") (pin "1") (pinfunction "1_1") (pintype "passive"))
    )
    (net (code "33") (name "MOUNT_H1") (class "Default")
      (node (ref "R1") (pin "1") (pinfunction "1_1") (pintype "passive"))
    )
    (net (code "34") (name "MOUNT_H2") (class "Default")
      (node (ref "C3") (pin "2") (pinfunction "2_2") (pintype "passive"))
    )
    (net (code "35") (name "Net-(+5V-PadA)") (class "Default")
      (node (ref "+5V") (pin "A") (pinfunction "A_A") (pintype "passive"))
      (node (ref "R7") (pin "2") (pinfunction "2_2") (pintype "passive"))
    )
    (net (code "36") (name "Net-(5VOUTA-S)") (class "Default")
      (node (ref "5VOUT") (pin "1") (pinfunction "S_1") (pintype "passive"))
      (node (ref "F1") (pin "1") (pinfunction "1_1") (pintype "passive"))
    )
    (net (code "37") (name "Net-(C5-Pad1)") (class "Default")
      (node (ref "C5") (pin "1") (pinfunction "1_1") (pintype "passive"))
      (node (ref "R3") (pin "2") (pinfunction "2_2") (pintype "passive"))
    )
    (net (code "38") (name "Net-(DIAG-PadA)") (class "Default")
      (node (ref "DIAG") (pin "A") (pinfunction "A_A") (pintype "passive"))
      (node (ref "R15") (pin "1") (pinfunction "1_1") (pintype "passive"))
    )
    (net (code "39") (name "Net-(DOOR-7)") (class "Default")
      (node (ref "DOOR") (pin "P$7") (pinfunction "7_P$7") (pintype "passive"))
      (node (ref "R9") (pin "1") (pinfunction "1_1") (pintype "passive"))
    )
    (net (code "40") (name "Net-(R5-Pad1)") (class "Default")
      (node (ref "R5") (pin "1") (pinfunction "1_1") (pintype "passive"))
      (node (ref "R6") (pin "2") (pinfunction "2_2") (pintype "passive"))
    )
    (net (code "41") (name "Net-(R14-Pad1)") (class "Default")
      (node (ref "R14") (pin "1") (pinfunction "1_1") (pintype "passive"))
      (node (ref "SYS") (pin "A") (pinfunction "A_A") (pintype "passive"))
    )
    (net (code "42") (name "Net-(R43-Pad2)") (class "Default")
      (node (ref "R43") (pin "2") (pinfunction "2_2") (pintype "passive"))
      (node (ref "USBPWR") (pin "A") (pinfunction "A_A") (pintype "passive"))
    )
    (net (code "43") (name "Net-(U1-BST)") (class "Default")
      (node (ref "C8") (pin "1") (pinfunction "1_1") (pintype "passive"))
      (node (ref "U1") (pin "8") (pinfunction "BST_8") (pintype "bidirectional"))
    )
    (net (code "44") (name "Net-(U1-COMP)") (class "Default")
      (node (ref "C5") (pin "2") (pinfunction "2_2") (pintype "passive"))
      (node (ref "U1") (pin "3") (pinfunction "COMP_3") (pintype "bidirectional"))
    )
    (net (code "45") (name "Net-(U1-FB)") (class "Default")
      (node (ref "R4") (pin "1") (pinfunction "1_1") (pintype "passive"))
      (node (ref "R5") (pin "2") (pinfunction "2_2") (pintype "passive"))
      (node (ref "U1") (pin "4") (pinfunction "FB_4") (pintype "bidirectional"))
    )
    (net (code "46") (name "Net-(U1-FREQ)") (class "Default")
      (node (ref "R2") (pin "2") (pinfunction "2_2") (pintype "passive"))
      (node (ref "U1") (pin "6") (pinfunction "FREQ_6") (pintype "bidirectional"))
    )
    (net (code "47") (name "Net-(U1-SW)") (class "Default")
      (node (ref "C8") (pin "2") (pinfunction "2_2") (pintype "passive"))
      (node (ref "D1") (pin "C") (pinfunction "C_C") (pintype "passive"))
      (node (ref "L1") (pin "1") (pinfunction "1_1") (pintype "bidirectional"))
      (node (ref "U1") (pin "1") (pinfunction "SW_1") (pintype "bidirectional"))
    )
    (net (code "48") (name "Net-(U3-AVCC)") (class "Default")
      (node (ref "C15") (pin "2") (pinfunction "2_2") (pintype "passive"))
      (node (ref "L3") (pin "2") (pinfunction "2_2") (pintype "passive"))
      (node (ref "U3") (pin "61") (pinfunction "AVCC_61") (pintype "power_in"))
    )
    (net (code "49") (name "Net-(U3-PR0)") (class "Default")
      (node (ref "R14") (pin "2") (pinfunction "2_2") (pintype "passive"))
      (node (ref "U3") (pin "58") (pinfunction "PR0_58") (pintype "bidirectional"))
    )
    (net (code "50") (name "Net-(U3-PR1)") (class "Default")
      (node (ref "R15") (pin "2") (pinfunction "2_2") (pintype "passive"))
      (node (ref "U3") (pin "59") (pinfunction "PR1_59") (pintype "bidirectional"))
    )
    (net (code "51") (name "Net-(U4-A)") (class "Default")
      (node (ref "PTC1") (pin "1") (pinfunction "1_1") (pintype "passive"))
      (node (ref "R16") (pin "1") (pinfunction "1_1") (pintype "passive"))
      (node (ref "U4") (pin "6") (pinfunction "A_6") (pintype "bidirectional"))
    )
    (net (code "52") (name "Net-(U4-B)") (class "Default")
      (node (ref "PTC2") (pin "1") (pinfunction "1_1") (pintype "passive"))
      (node (ref "R17") (pin "2") (pinfunction "2_2") (pintype "passive"))
      (node (ref "U4") (pin "7") (pinfunction "B_7") (pintype "bidirectional"))
    )
    (net (code "53") (name "Net-(U5-G)") (class "Default")
      (node (ref "R11") (pin "2") (pinfunction "2_2") (pintype "passive"))
      (node (ref "U5") (pin "1") (pinfunction "G_1") (pintype "passive"))
    )
    (net (code "54") (name "Net-(U7-3V3OUT)") (class "Default")
      (node (ref "C43") (pin "1") (pinfunction "1_1") (pintype "passive"))
      (node (ref "R42") (pin "2") (pinfunction "2_2") (pintype "passive"))
      (node (ref "U7") (pin "3") (pinfunction "3V3OUT_3") (pintype "output"))
      (node (ref "U7") (pin "9") (pinfunction "VCCIO_9") (pintype "input"))
    )
    (net (code "55") (name "Net-(U7-CBUS0)") (class "Default")
      (node (ref "U7") (pin "6") (pinfunction "CBUS0_6") (pintype "bidirectional"))
      (node (ref "U8") (pin "2") (pinfunction "~{RE}_2") (pintype "input"))
      (node (ref "U8") (pin "3") (pinfunction "DE_3") (pintype "input"))
    )
    (net (code "56") (name "Net-(U7-RXD)") (class "Default")
      (node (ref "U7") (pin "10") (pinfunction "RXD_10") (pintype "input"))
      (node (ref "U8") (pin "1") (pinfunction "RO_1") (pintype "output"))
    )
    (net (code "57") (name "Net-(U7-TXD)") (class "Default")
      (node (ref "U7") (pin "7") (pinfunction "TXD_7") (pintype "output"))
      (node (ref "U8") (pin "4") (pinfunction "DI_4") (pintype "input"))
    )
    (net (code "58") (name "Net-(U7-USBDM)") (class "Default")
      (node (ref "R31") (pin "2") (pinfunction "2_2") (pintype "passive"))
      (node (ref "U7") (pin "1") (pinfunction "USBDM_1") (pintype "bidirectional"))
    )
    (net (code "59") (name "Net-(U7-USBDP)") (class "Default")
      (node (ref "R41") (pin "2") (pinfunction "2_2") (pintype "passive"))
      (node (ref "U7") (pin "12") (pinfunction "USBDP_12") (pintype "bidirectional"))
    )
    (net (code "60") (name "Net-(U7-~{RESET})") (class "Default")
      (node (ref "R42") (pin "1") (pinfunction "1_1") (pintype "passive"))
      (node (ref "U7") (pin "2") (pinfunction "~{RESET}_2") (pintype "input"))
    )
    (net (code "61") (name "Net-(U9-CPA)") (class "Default")
      (node (ref "C6") (pin "1") (pinfunction "1_1") (pintype "passive"))
      (node (ref "U9") (pin "20") (pinfunction "CPA_20") (pintype "bidirectional"))
    )
    (net (code "62") (name "Net-(U9-CPB)") (class "Default")
      (node (ref "C6") (pin "2") (pinfunction "2_2") (pintype "passive"))
      (node (ref "U9") (pin "21") (pinfunction "CPB_21") (pintype "bidirectional"))
    )
    (net (code "63") (name "Net-(U9-VCP)") (class "Default")
      (node (ref "C11") (pin "1") (pinfunction "1_1") (pintype "passive"))
      (node (ref "U9") (pin "19") (pinfunction "VCP_19") (pintype "bidirectional"))
    )
    (net (code "64") (name "Net-(U9-VG)") (class "Default")
      (node (ref "C20") (pin "1") (pinfunction "1_1") (pintype "passive"))
      (node (ref "U9") (pin "14") (pinfunction "VG_14") (pintype "bidirectional"))
    )
    (net (code "65") (name "Net-(U11-ILIM)") (class "Default")
      (node (ref "R40") (pin "2") (pinfunction "2_2") (pintype "passive"))
      (node (ref "U11") (pin "4") (pinfunction "ILIM_4") (pintype "bidirectional"))
    )
    (net (code "66") (name "Net-(U12-+IN)") (class "Default")
      (node (ref "R18") (pin "2") (pinfunction "2_2") (pintype "passive"))
      (node (ref "R19") (pin "2") (pinfunction "2_2") (pintype "passive"))
      (node (ref "U12") (pin "3") (pinfunction "+IN_3") (pintype "input"))
    )
    (net (code "67") (name "PDI_CLK") (class "Default")
      (node (ref "PDI") (pin "5") (pinfunction "5_5") (pintype "passive"))
      (node (ref "R13") (pin "1") (pinfunction "1_1") (pintype "passive"))
      (node (ref "U3") (pin "57") (pinfunction "~{RESET}/PDI_57") (pintype "bidirectional"))
    )
    (net (code "68") (name "PDI_DATA") (class "Default")
      (node (ref "PDI") (pin "1") (pinfunction "1_1") (pintype "passive"))
      (node (ref "U3") (pin "56") (pinfunction "PDI_56") (pintype "bidirectional"))
    )
    (net (code "69") (name "PE7") (class "Default")
      (node (ref "S3") (pin "P$7") (pinfunction "7_P$7") (pintype "passive"))
      (node (ref "U3") (pin "43") (pinfunction "PE7_43") (pintype "bidirectional"))
    )
    (net (code "70") (name "PF3") (class "Default")
      (node (ref "S3") (pin "P$8") (pinfunction "8_P$8") (pintype "passive"))
      (node (ref "U3") (pin "49") (pinfunction "PF3_49") (pintype "bidirectional"))
    )
    (net (code "71") (name "PF4") (class "Default")
      (node (ref "S3") (pin "P$9") (pinfunction "9_P$9") (pintype "passive"))
      (node (ref "U3") (pin "50") (pinfunction "PF4_50") (pintype "bidirectional"))
    )
    (net (code "72") (name "PF5") (class "Default")
      (node (ref "S3") (pin "P$10") (pinfunction "10_P$10") (pintype "passive"))
      (node (ref "U3") (pin "51") (pinfunction "PF5_51") (pintype "bidirectional"))
    )
    (net (code "73") (name "PF6") (class "Default")
      (node (ref "S3") (pin "P$11") (pinfunction "11_P$11") (pintype "passive"))
      (node (ref "U3") (pin "54") (pinfunction "PF6_54") (pintype "bidirectional"))
    )
    (net (code "74") (name "PF7") (class "Default")
      (node (ref "S3") (pin "P$12") (pinfunction "12_P$12") (pintype "passive"))
      (node (ref "U3") (pin "55") (pinfunction "PF7_55") (pintype "bidirectional"))
    )
    (net (code "75") (name "PWMA") (class "Default")
      (node (ref "U3") (pin "18") (pinfunction "PC2_18") (pintype "bidirectional"))
      (node (ref "U9") (pin "6") (pinfunction "PWMA/HSA_6") (pintype "bidirectional"))
    )
    (net (code "76") (name "PWMB") (class "Default")
      (node (ref "U3") (pin "17") (pinfunction "PC1_17") (pintype "bidirectional"))
      (node (ref "U9") (pin "7") (pinfunction "PWMB/HSB_7") (pintype "bidirectional"))
    )
    (net (code "77") (name "PWMC") (class "Default")
      (node (ref "U3") (pin "16") (pinfunction "PC0_16") (pintype "bidirectional"))
      (node (ref "U9") (pin "8") (pinfunction "PWMC/HSC_8") (pintype "bidirectional"))
    )
    (net (code "78") (name "SCLK") (class "Default")
      (node (ref "J2") (pin "2") (pinfunction "S_2") (pintype "passive"))
      (node (ref "U3") (pin "40") (pinfunction "PE4_40") (pintype "bidirectional"))
    )
    (net (code "79") (name "SDA") (class "Default")
      (node (ref "J2") (pin "3") (pinfunction "S_3") (pintype "passive"))
      (node (ref "U3") (pin "41") (pinfunction "PE5_41") (pintype "bidirectional"))
    )
    (net (code "80") (name "SOA") (class "Default")
      (node (ref "C16") (pin "1") (pinfunction "1_1") (pintype "passive"))
      (node (ref "RN1") (pin "6") (pinfunction "2_6") (pintype "passive"))
      (node (ref "U3") (pin "63") (pinfunction "PA1_63") (pintype "bidirectional"))
      (node (ref "U9") (pin "15") (pinfunction "SOA_15") (pintype "bidirectional"))
    )
    (net (code "81") (name "SOB") (class "Default")
      (node (ref "C17") (pin "1") (pinfunction "1_1") (pintype "passive"))
      (node (ref "RN1") (pin "7") (pinfunction "2_7") (pintype "passive"))
      (node (ref "U3") (pin "64") (pinfunction "PA2_64") (pintype "bidirectional"))
      (node (ref "U9") (pin "16") (pinfunction "SOB_16") (pintype "bidirectional"))
    )
    (net (code "82") (name "SOC") (class "Default")
      (node (ref "C18") (pin "1") (pinfunction "1_1") (pintype "passive"))
      (node (ref "RN1") (pin "8") (pinfunction "2_8") (pintype "passive"))
      (node (ref "U3") (pin "1") (pinfunction "PA3_1") (pintype "bidirectional"))
      (node (ref "U9") (pin "17") (pinfunction "SOC_17") (pintype "bidirectional"))
    )
    (net (code "83") (name "SYNC") (class "Default")
      (node (ref "DOOR") (pin "P$5") (pinfunction "5_P$5") (pintype "passive"))
      (node (ref "DOOR") (pin "P$6") (pinfunction "6_P$6") (pintype "passive"))
    )
    (net (code "84") (name "USBDN1_DM") (class "Default")
      (node (ref "R31") (pin "1") (pinfunction "1_1") (pintype "passive"))
      (node (ref "USBUP") (pin "D-") (pinfunction "D-_D-") (pintype "bidirectional"))
    )
    (net (code "85") (name "USBDN1_DP") (class "Default")
      (node (ref "R41") (pin "1") (pinfunction "1_1") (pintype "passive"))
      (node (ref "USBUP") (pin "D+") (pinfunction "D+_D+") (pintype "bidirectional"))
    )
    (net (code "86") (name "USBGND") (class "Default")
      (node (ref "C25") (pin "2") (pinfunction "2_2") (pintype "passive"))
      (node (ref "C28") (pin "1") (pinfunction "1_1") (pintype "passive"))
      (node (ref "C43") (pin "2") (pinfunction "2_2") (pintype "passive"))
      (node (ref "C44") (pin "2") (pinfunction "2_2") (pintype "passive"))
      (node (ref "C45") (pin "2") (pinfunction "2_2") (pintype "passive"))
      (node (ref "FB1") (pin "1") (pinfunction "1_1") (pintype "passive"))
      (node (ref "U6") (pin "1") (pinfunction "GND_1") (pintype "passive"))
      (node (ref "U7") (pin "13") (pinfunction "GND_13") (pintype "power_in"))
      (node (ref "U7") (pin "5") (pinfunction "GND_5") (pintype "power_in"))
      (node (ref "U8") (pin "5") (pinfunction "GND_5") (pintype "passive"))
      (node (ref "USBPWR") (pin "C") (pinfunction "C_C") (pintype "passive"))
      (node (ref "USBUP") (pin "GND") (pinfunction "GND_GND") (pintype "bidirectional"))
      (node (ref "USBUP") (pin "S1") (pinfunction "S1_S1") (pintype "bidirectional"))
      (node (ref "USBUP") (pin "S2") (pinfunction "S2_S2") (pintype "bidirectional"))
    )
    (net (code "87") (name "VBUS") (class "Default")
      (node (ref "C25") (pin "1") (pinfunction "1_1") (pintype "passive"))
      (node (ref "C44") (pin "1") (pinfunction "1_1") (pintype "passive"))
      (node (ref "R43") (pin "1") (pinfunction "1_1") (pintype "passive"))
      (node (ref "U6") (pin "3") (pinfunction "VIN_3") (pintype "input"))
      (node (ref "U7") (pin "4") (pinfunction "VCC_4") (pintype "power_in"))
      (node (ref "USBUP") (pin "VBUS") (pinfunction "VBUS_VBUS") (pintype "bidirectional"))
    )
    (net (code "88") (name "VBUS_3V3") (class "Default")
      (node (ref "C28") (pin "2") (pinfunction "2_2") (pintype "passive"))
      (node (ref "C45") (pin "1") (pinfunction "1_1") (pintype "passive"))
      (node (ref "U6") (pin "2") (pinfunction "VOUT_2") (pintype "output"))
      (node (ref "U8") (pin "8") (pinfunction "VCC_8") (pintype "power_in"))
    )
    (net (code "89") (name "VREF") (class "Default")
      (node (ref "C13") (pin "1") (pinfunction "1_1") (pintype "passive"))
      (node (ref "C19") (pin "1") (pinfunction "1_1") (pintype "passive"))
      (node (ref "R18") (pin "1") (pinfunction "1_1") (pintype "passive"))
      (node (ref "R20") (pin "1") (pinfunction "1_1") (pintype "passive"))
      (node (ref "U10") (pin "1") (pinfunction "REF_1") (pintype "power_in"))
      (node (ref "U10") (pin "2") (pinfunction "CATHODE_2") (pintype "passive"))
      (node (ref "U3") (pin "62") (pinfunction "PA0_62") (pintype "bidirectional"))
    )
    (net (code "90") (name "VREF_1V25") (class "Default")
      (node (ref "RN1") (pin "1") (pinfunction "1_1") (pintype "passive"))
      (node (ref "RN1") (pin "2") (pinfunction "1_2") (pintype "passive"))
      (node (ref "RN1") (pin "3") (pinfunction "1_3") (pintype "passive"))
      (node (ref "U12") (pin "1") (pinfunction "OUT_1") (pintype "output"))
      (node (ref "U12") (pin "4") (pinfunction "-IN_4") (pintype "input"))
    )
    (net (code "91") (name "WS2813+5V") (class "Default")
      (node (ref "F2") (pin "1") (pinfunction "1_1") (pintype "passive"))
      (node (ref "R12") (pin "2") (pinfunction "2_2") (pintype "passive"))
      (node (ref "WS2813") (pin "1") (pinfunction "S_1") (pintype "passive"))
    )
    (net (code "92") (name "WS2813_CTRL") (class "Default")
      (node (ref "R11") (pin "1") (pinfunction "1_1") (pintype "passive"))
      (node (ref "U3") (pin "26") (pinfunction "PD0_26") (pintype "bidirectional"))
    )
    (net (code "93") (name "WS2813_MO") (class "Default")
      (node (ref "R12") (pin "1") (pinfunction "1_1") (pintype "passive"))
      (node (ref "U5") (pin "3") (pinfunction "D_3") (pintype "passive"))
      (node (ref "WS2813") (pin "3") (pinfunction "S_3") (pintype "passive"))
      (node (ref "WS2813") (pin "4") (pinfunction "S_4") (pintype "passive"))
    )
    (net (code "94") (name "unconnected-(PDI-Pad3)") (class "Default")
      (node (ref "PDI") (pin "3") (pinfunction "3_3") (pintype "passive"))
    )
    (net (code "95") (name "unconnected-(PDI-Pad4)") (class "Default")
      (node (ref "PDI") (pin "4") (pinfunction "4_4") (pintype "passive"))
    )
    (net (code "96") (name "unconnected-(U1-EN-Pad2)") (class "Default")
      (node (ref "U1") (pin "2") (pinfunction "EN_2") (pintype "bidirectional"))
    )
    (net (code "97") (name "unconnected-(U3-PA7-Pad5)") (class "Default")
      (node (ref "U3") (pin "5") (pinfunction "PA7_5") (pintype "bidirectional"))
    )
    (net (code "98") (name "unconnected-(U3-PB0-Pad6)") (class "Default")
      (node (ref "U3") (pin "6") (pinfunction "PB0_6") (pintype "bidirectional"))
    )
    (net (code "99") (name "unconnected-(U3-PB1-Pad7)") (class "Default")
      (node (ref "U3") (pin "7") (pinfunction "PB1_7") (pintype "bidirectional"))
    )
    (net (code "100") (name "unconnected-(U3-PB2-Pad8)") (class "Default")
      (node (ref "U3") (pin "8") (pinfunction "PB2_8") (pintype "bidirectional"))
    )
    (net (code "101") (name "unconnected-(U3-PB3-Pad9)") (class "Default")
      (node (ref "U3") (pin "9") (pinfunction "PB3_9") (pintype "bidirectional"))
    )
    (net (code "102") (name "unconnected-(U3-PB4-Pad10)") (class "Default")
      (node (ref "U3") (pin "10") (pinfunction "PB4_10") (pintype "bidirectional"))
    )
    (net (code "103") (name "unconnected-(U3-PB5-Pad11)") (class "Default")
      (node (ref "U3") (pin "11") (pinfunction "PB5_11") (pintype "bidirectional"))
    )
    (net (code "104") (name "unconnected-(U3-PB6-Pad12)") (class "Default")
      (node (ref "U3") (pin "12") (pinfunction "PB6_12") (pintype "bidirectional"))
    )
    (net (code "105") (name "unconnected-(U3-PB7-Pad13)") (class "Default")
      (node (ref "U3") (pin "13") (pinfunction "PB7_13") (pintype "bidirectional"))
    )
    (net (code "106") (name "unconnected-(U3-PE0-Pad36)") (class "Default")
      (node (ref "U3") (pin "36") (pinfunction "PE0_36") (pintype "bidirectional"))
    )
    (net (code "107") (name "unconnected-(U3-PE1-Pad37)") (class "Default")
      (node (ref "U3") (pin "37") (pinfunction "PE1_37") (pintype "bidirectional"))
    )
    (net (code "108") (name "unconnected-(U3-PE2-Pad38)") (class "Default")
      (node (ref "U3") (pin "38") (pinfunction "PE2_38") (pintype "bidirectional"))
    )
    (net (code "109") (name "unconnected-(U3-PE3-Pad39)") (class "Default")
      (node (ref "U3") (pin "39") (pinfunction "PE3_39") (pintype "bidirectional"))
    )
    (net (code "110") (name "unconnected-(U3-PE6-Pad42)") (class "Default")
      (node (ref "U3") (pin "42") (pinfunction "PE6_42") (pintype "bidirectional"))
    )
    (net (code "111") (name "unconnected-(U7-~{CTS}-Pad11)") (class "Default")
      (node (ref "U7") (pin "11") (pinfunction "~{CTS}_11") (pintype "input"))
    )
    (net (code "112") (name "unconnected-(U7-~{RTS}-Pad8)") (class "Default")
      (node (ref "U7") (pin "8") (pinfunction "~{RTS}_8") (pintype "output"))
    )
    (net (code "113") (name "~{FAULT}") (class "Default")
      (node (ref "U3") (pin "23") (pinfunction "PC7_23") (pintype "bidirectional"))
      (node (ref "U9") (pin "1") (pinfunction "~{FAULT}_1") (pintype "bidirectional"))
    )
    (net (code "114") (name "~{SLEEP}") (class "Default")
      (node (ref "U3") (pin "22") (pinfunction "PC6_22") (pintype "bidirectional"))
      (node (ref "U9") (pin "2") (pinfunction "~{SLEEP}_2") (pintype "bidirectional"))
    )
  )
)
